# Sensors.net
KiCad netlist of a schematic drawn in Altium Designer
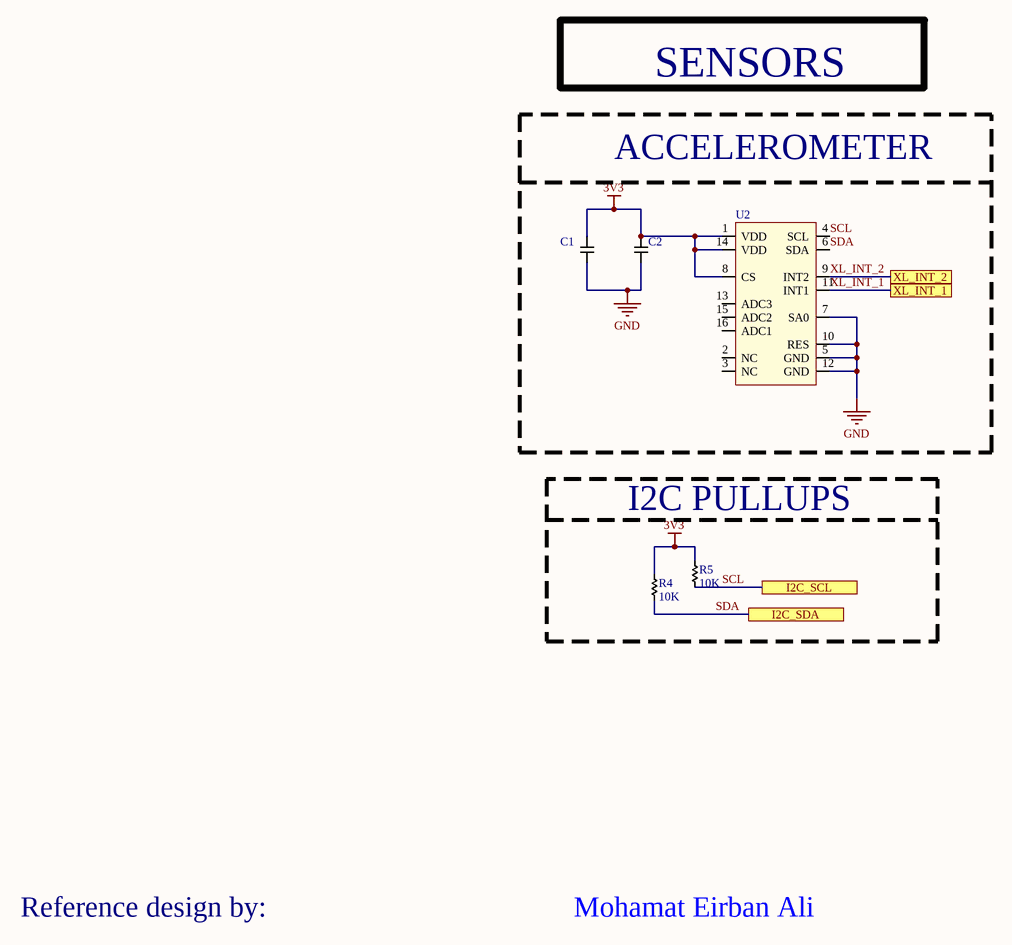
[diagram p0: Sensors.SchDoc]

(export (version "E")
  (design (tool "Eeschema 10.0.6"))
  (components
    (comp (ref "C1")
      (value "~")
      (footprint "CAP_0603_HIGH")
      (description "0603 Capacitor")
      (fields (field (name "TOLERANCE") "20%"))
      (libsource (lib "smarchWatch_V5") (part "Capacitor_0603"))
    )
    (comp (ref "C2")
      (value "~")
      (footprint "CAP_0603_HIGH")
      (description "0603 Capacitor")
      (fields (field (name "TOLERANCE") "20%") (field (name "VOLTAGE") "6.3V"))
      (libsource (lib "smarchWatch_V5") (part "Capacitor_0603"))
    )
    (comp (ref "R4")
      (value "10K")
      (footprint "RES_0603_HIGH")
      (description "0603 Resistor")
      (libsource (lib "smarchWatch_V5") (part "Resistor_0603_3"))
    )
    (comp (ref "R5")
      (value "10K")
      (footprint "RES_0603_HIGH")
      (description "0603 Resistor")
      (libsource (lib "smarchWatch_V5") (part "Resistor_0603_3"))
    )
    (comp (ref "U2")
      (value "~")
      (footprint "LIS3DH")
      (description "LIS3DH ACCEL 2-16G I2C/SPI 16LGA")
      (libsource (lib "smarchWatch_V5") (part "LIS3DH"))
    )
  )
  (nets
    (net (code "1") (name "/SCL") (class "Default")
      (node (ref "R5") (pin "1") (pinfunction "1_1") (pintype "passive"))
      (node (ref "U2") (pin "4") (pinfunction "SCL_4") (pintype "passive"))
    )
    (net (code "2") (name "/SDA") (class "Default")
      (node (ref "R4") (pin "1") (pinfunction "1_1") (pintype "passive"))
      (node (ref "U2") (pin "6") (pinfunction "SDA_6") (pintype "passive"))
    )
    (net (code "3") (name "/XL_INT_1") (class "Default")
      (node (ref "U2") (pin "11") (pinfunction "INT1_11") (pintype "passive"))
    )
    (net (code "4") (name "/XL_INT_2") (class "Default")
      (node (ref "U2") (pin "9") (pinfunction "INT2_9") (pintype "passive"))
    )
    (net (code "5") (name "3V3") (class "Default")
      (node (ref "C1") (pin "1") (pinfunction "1_1") (pintype "passive"))
      (node (ref "C2") (pin "1") (pinfunction "1_1") (pintype "passive"))
      (node (ref "R4") (pin "2") (pinfunction "2_2") (pintype "passive"))
      (node (ref "R5") (pin "2") (pinfunction "2_2") (pintype "passive"))
      (node (ref "U2") (pin "1") (pinfunction "VDD_1") (pintype "passive"))
      (node (ref "U2") (pin "14") (pinfunction "VDD_14") (pintype "passive"))
      (node (ref "U2") (pin "8") (pinfunction "CS_8") (pintype "passive"))
    )
    (net (code "6") (name "GND") (class "Default")
      (node (ref "C1") (pin "2") (pinfunction "2_2") (pintype "passive"))
      (node (ref "C2") (pin "2") (pinfunction "2_2") (pintype "passive"))
      (node (ref "U2") (pin "10") (pinfunction "RES_10") (pintype "passive"))
      (node (ref "U2") (pin "12") (pinfunction "GND_12") (pintype "passive"))
      (node (ref "U2") (pin "5") (pinfunction "GND_5") (pintype "passive"))
      (node (ref "U2") (pin "7") (pinfunction "SA0_7") (pintype "passive"))
    )
    (net (code "7") (name "unconnected-(U2-ADC1-Pad16)") (class "Default")
      (node (ref "U2") (pin "16") (pinfunction "ADC1_16") (pintype "passive"))
    )
    (net (code "8") (name "unconnected-(U2-ADC2-Pad15)") (class "Default")
      (node (ref "U2") (pin "15") (pinfunction "ADC2_15") (pintype "passive"))
    )
    (net (code "9") (name "unconnected-(U2-ADC3-Pad13)") (class "Default")
      (node (ref "U2") (pin "13") (pinfunction "ADC3_13") (pintype "passive"))
    )
    (net (code "10") (name "unconnected-(U2-NC-Pad2)") (class "Default")
      (node (ref "U2") (pin "2") (pinfunction "NC_2") (pintype "passive"))
    )
    (net (code "11") (name "unconnected-(U2-NC-Pad3)") (class "Default")
      (node (ref "U2") (pin "3") (pinfunction "NC_3") (pintype "passive"))
    )
  )
)
